# barometer.net
KiCad netlist of a schematic drawn in Altium Designer
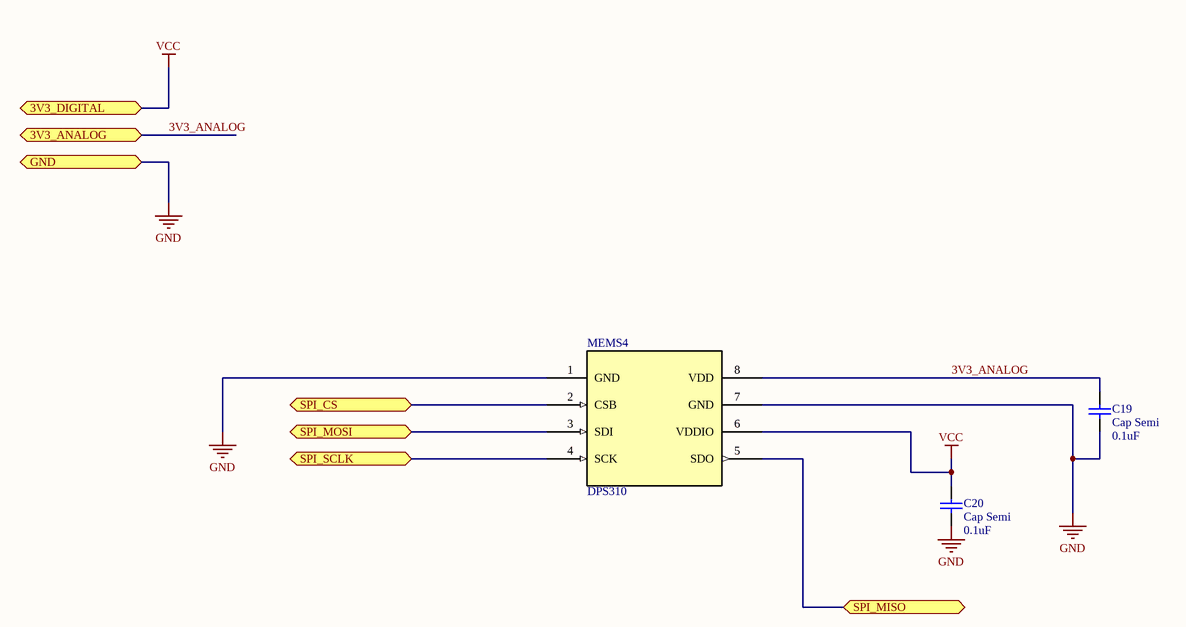
[diagram p0: barometer.SchDoc]

(export (version "E")
  (design (tool "Eeschema 10.0.6"))
  (components
    (comp (ref "C19")
      (value "Cap Semi")
      (footprint "C1206")
      (description "Capacitor (Semiconductor SIM Model)")
      (fields (field (name "ALTIUM_VALUE") "0.1uF") (field (name "PUBLISHER") "Altium Limited"))
      (libsource (lib "Miscellaneous Devices") (part "Cap Semi"))
    )
    (comp (ref "C20")
      (value "Cap Semi")
      (footprint "C1206")
      (description "Capacitor (Semiconductor SIM Model)")
      (fields (field (name "ALTIUM_VALUE") "0.1uF") (field (name "PUBLISHER") "Altium Limited"))
      (libsource (lib "Miscellaneous Devices") (part "Cap Semi"))
    )
    (comp (ref "MEMS4")
      (value "DPS310")
      (footprint "PG-VLGA-8-1")
      (libsource (lib "RPi_sensor_expansion_board_library") (part "DPS310"))
    )
  )
  (nets
    (net (code "1") (name "/3V3_ANALOG") (class "Default")
      (node (ref "C19") (pin "2") (pinfunction "2_2") (pintype "passive"))
      (node (ref "MEMS4") (pin "8") (pinfunction "VDD_8") (pintype "power_in"))
    )
    (net (code "2") (name "/SPI_CS") (class "Default")
      (node (ref "MEMS4") (pin "2") (pinfunction "CSB_2") (pintype "input"))
    )
    (net (code "3") (name "/SPI_MISO") (class "Default")
      (node (ref "MEMS4") (pin "5") (pinfunction "SDO_5") (pintype "output"))
    )
    (net (code "4") (name "/SPI_MOSI") (class "Default")
      (node (ref "MEMS4") (pin "3") (pinfunction "SDI_3") (pintype "input"))
    )
    (net (code "5") (name "/SPI_SCLK") (class "Default")
      (node (ref "MEMS4") (pin "4") (pinfunction "SCK_4") (pintype "input"))
    )
    (net (code "6") (name "GND") (class "Default")
      (node (ref "C19") (pin "1") (pinfunction "1_1") (pintype "passive"))
      (node (ref "C20") (pin "1") (pinfunction "1_1") (pintype "passive"))
      (node (ref "MEMS4") (pin "1") (pinfunction "GND_1") (pintype "power_in"))
      (node (ref "MEMS4") (pin "7") (pinfunction "GND_7") (pintype "power_in"))
    )
    (net (code "7") (name "VCC") (class "Default")
      (node (ref "C20") (pin "2") (pinfunction "2_2") (pintype "passive"))
      (node (ref "MEMS4") (pin "6") (pinfunction "VDDIO_6") (pintype "passive"))
    )
  )
)
